# tick-mini-mk-4_2.net
KiCad netlist of a schematic drawn in EAGLE
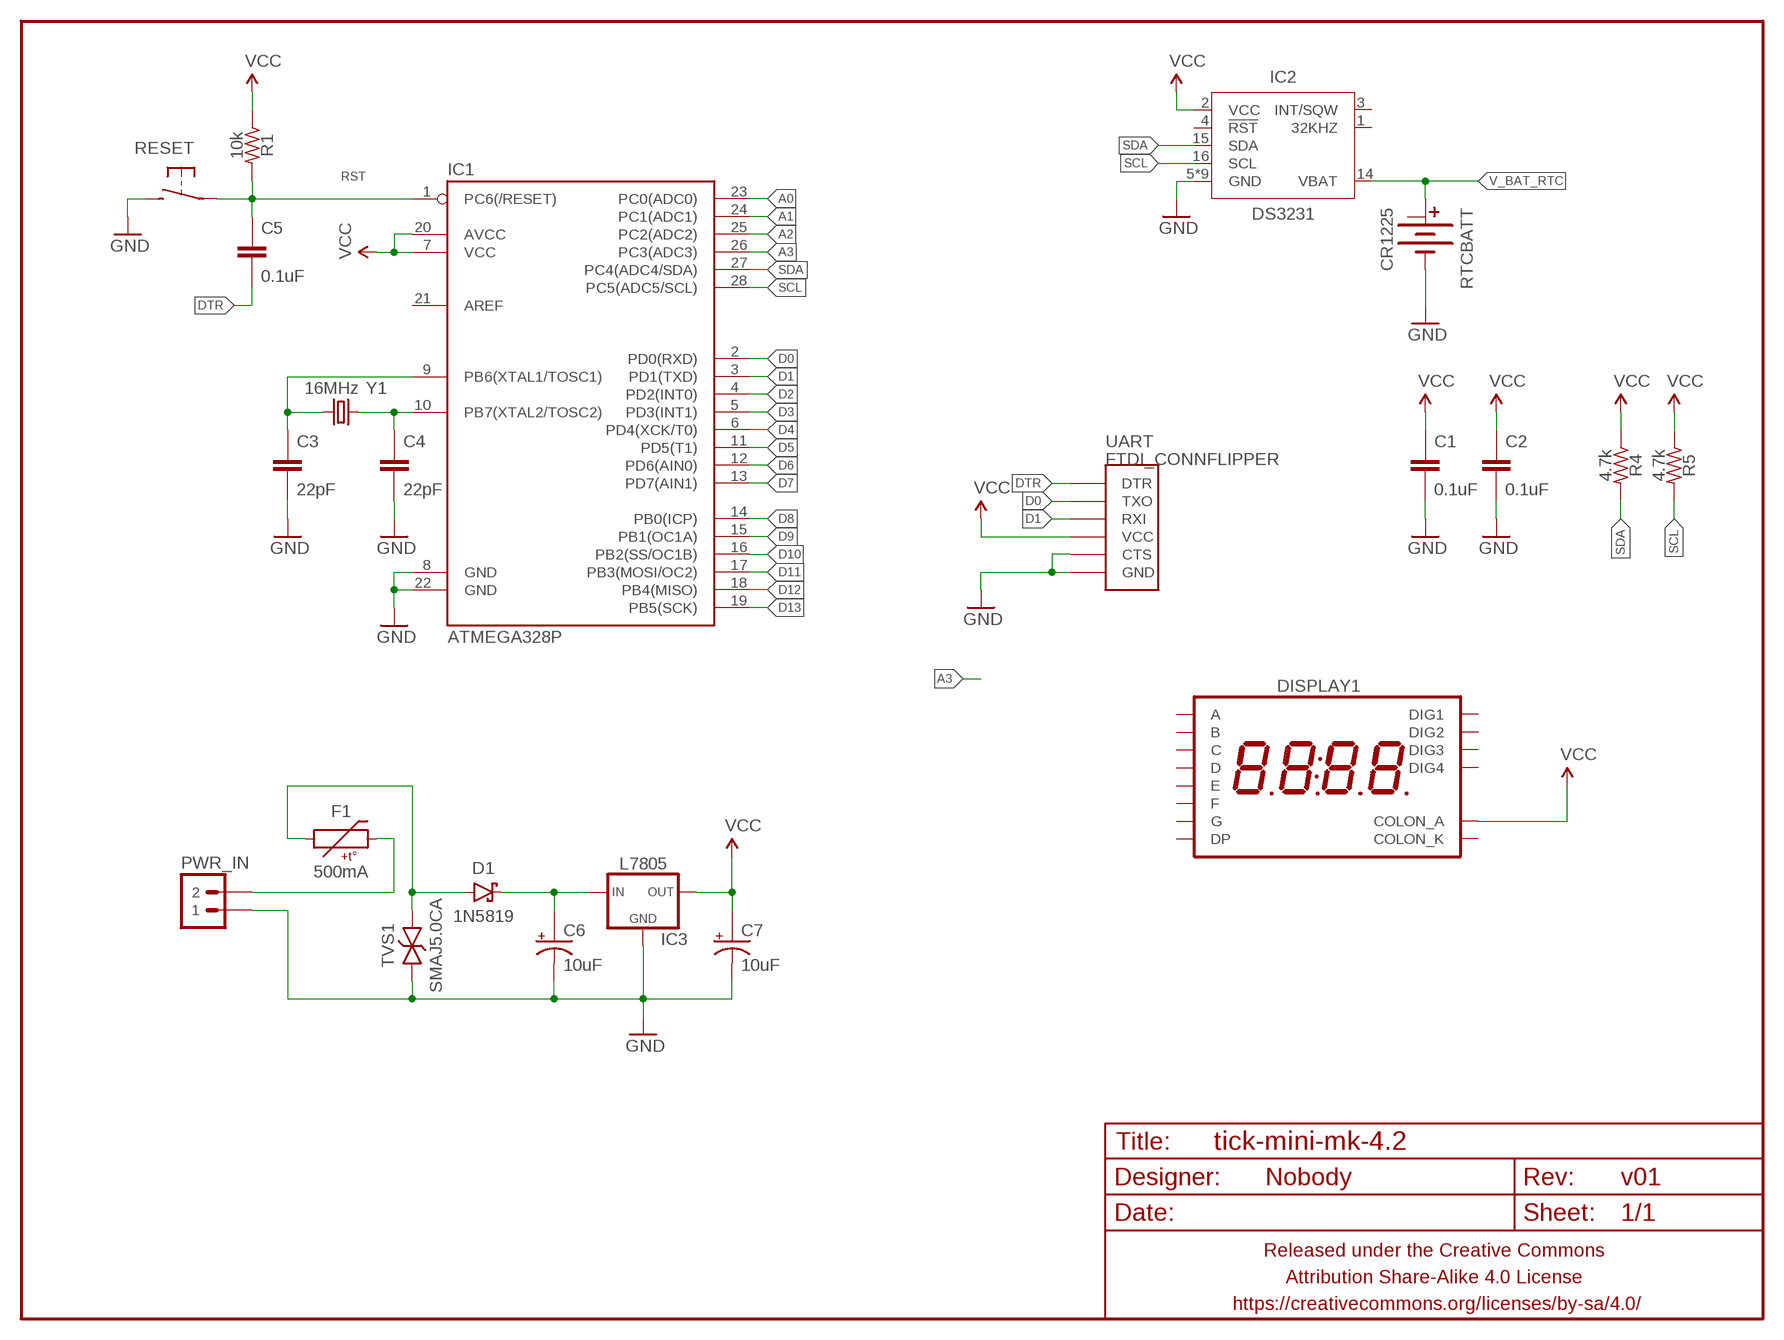
[diagram p0: schematic, sheet 1]

(export (version "E")
  (design (tool "Eeschema 10.0.6"))
  (components
    (comp (ref "C1")
      (value "0.1uF")
      (footprint "eagle-import:C025-024X044")
      (libsource (lib "eagle-import") (part "CAPACITOR-CERAMIC025-024X044"))
    )
    (comp (ref "C2")
      (value "0.1uF")
      (footprint "eagle-import:C025-024X044")
      (libsource (lib "eagle-import") (part "CAPACITOR-CERAMIC025-024X044"))
    )
    (comp (ref "C3")
      (value "22pF")
      (footprint "eagle-import:C025-024X044")
      (libsource (lib "eagle-import") (part "CAPACITOR-CERAMIC025-024X044"))
    )
    (comp (ref "C4")
      (value "22pF")
      (footprint "eagle-import:C025-024X044")
      (libsource (lib "eagle-import") (part "CAPACITOR-CERAMIC025-024X044"))
    )
    (comp (ref "C5")
      (value "0.1uF")
      (footprint "eagle-import:C025-024X044")
      (libsource (lib "eagle-import") (part "CAPACITOR-CERAMIC025-024X044"))
    )
    (comp (ref "C6")
      (value "10uF")
      (footprint "eagle-import:E2-5")
      (libsource (lib "eagle-import") (part "CAPACITOR-POLARIZEDE2-5"))
    )
    (comp (ref "C7")
      (value "10uF")
      (footprint "eagle-import:E2-5")
      (libsource (lib "eagle-import") (part "CAPACITOR-POLARIZEDE2-5"))
    )
    (comp (ref "D1")
      (value "1N5819")
      (footprint "eagle-import:DIODE-10.16MM")
      (libsource (lib "eagle-import") (part "DIODE-SCHOTTKYPTH-10.16MM"))
    )
    (comp (ref "DISPLAY1")
      (value "7SEG_4DIGIT_COLON14.2MM-CC-NS")
      (footprint "eagle-import:7SEG_4DIG_NS")
      (libsource (lib "eagle-import") (part "7SEG_4DIGIT_COLON14.2MM-CC-NS"))
    )
    (comp (ref "F1")
      (value "500mA")
      (footprint "eagle-import:PTC-PTH-5.08MM")
      (libsource (lib "eagle-import") (part "PTCPTH-5.08MM"))
    )
    (comp (ref "FRAME1")
      (value "FRAME-LETTERNO_PACKAGE")
      (footprint "eagle-import:DUMMY")
      (fields (field (name "DESIGNER") "Nobody"))
      (libsource (lib "eagle-import") (part "FRAME-LETTERNO_PACKAGE"))
    )
    (comp (ref "IC1")
      (value "ATMEGA328P")
      (footprint "eagle-import:DIL28-3")
      (libsource (lib "eagle-import") (part "ATMEGA328P_PDIP"))
    )
    (comp (ref "IC2")
      (value "DS3231")
      (footprint "eagle-import:SO16W")
      (libsource (lib "eagle-import") (part "DS3231"))
    )
    (comp (ref "IC3")
      (value "L7805")
      (footprint "eagle-import:TO-92-AMMO")
      (libsource (lib "eagle-import") (part "V_REG_78XXTO-92-INLINE"))
    )
    (comp (ref "PWR_IN")
      (value "M02JST-PTH-RA-R+")
      (footprint "eagle-import:JST-2-PH-RA-PTH-R+")
      (libsource (lib "eagle-import") (part "M02JST-PTH-RA-R+"))
    )
    (comp (ref "R1")
      (value "10k")
      (footprint "eagle-import:RESISTOR-AXIAL-PTH-5.08MM")
      (libsource (lib "eagle-import") (part "RESISTORPTH-AXIAL-5.08MM"))
    )
    (comp (ref "R4")
      (value "4.7k")
      (footprint "eagle-import:RESISTOR-AXIAL-PTH-5.08MM")
      (libsource (lib "eagle-import") (part "RESISTORPTH-AXIAL-5.08MM"))
    )
    (comp (ref "R5")
      (value "4.7k")
      (footprint "eagle-import:RESISTOR-AXIAL-PTH-5.08MM")
      (libsource (lib "eagle-import") (part "RESISTORPTH-AXIAL-5.08MM"))
    )
    (comp (ref "RESET")
      (value "SPST-NO-TACT3MM-PTH-SMALL-PADS")
      (footprint "eagle-import:DTS-3-SMALL-PADS")
      (libsource (lib "eagle-import") (part "SPST-NO-TACT3MM-PTH-SMALL-PADS"))
    )
    (comp (ref "RTCBATT")
      (value "CR1225")
      (footprint "eagle-import:BATTCON_12MM_SMD")
      (libsource (lib "eagle-import") (part "BATTERY-COINCR1225_SMD_SMALLER"))
    )
    (comp (ref "TVS1")
      (value "SMAJ5.0CA")
      (footprint "eagle-import:DO-41-TVS-BI-10.16MM")
      (libsource (lib "eagle-import") (part "TVSDO-41-10.16MM"))
    )
    (comp (ref "UART")
      (value "FTDI_CONNFLIPPER")
      (footprint "eagle-import:FTDI_CONN_FLIP")
      (libsource (lib "eagle-import") (part "FTDI_CONNFLIPPER"))
    )
    (comp (ref "Y1")
      (value "16MHz")
      (footprint "eagle-import:HC49U-V")
      (libsource (lib "eagle-import") (part "CRYSTALHC49UV"))
    )
  )
  (nets
    (net (code "1") (name "/RST") (class "Default")
      (node (ref "C5") (pin "1") (pinfunction "1_1") (pintype "passive"))
      (node (ref "IC1") (pin "1") (pinfunction "PC6(/RESET)_1") (pintype "bidirectional"))
      (node (ref "R1") (pin "P$2") (pinfunction "2_P$2") (pintype "passive"))
      (node (ref "RESET") (pin "1") (pinfunction "1_1") (pintype "passive"))
    )
    (net (code "2") (name "A0") (class "Default")
      (node (ref "IC1") (pin "23") (pinfunction "PC0(ADC0)_23") (pintype "bidirectional"))
    )
    (net (code "3") (name "A1") (class "Default")
      (node (ref "IC1") (pin "24") (pinfunction "PC1(ADC1)_24") (pintype "bidirectional"))
    )
    (net (code "4") (name "A2") (class "Default")
      (node (ref "IC1") (pin "25") (pinfunction "PC2(ADC2)_25") (pintype "bidirectional"))
    )
    (net (code "5") (name "A3") (class "Default")
      (node (ref "IC1") (pin "26") (pinfunction "PC3(ADC3)_26") (pintype "bidirectional"))
    )
    (net (code "6") (name "D0") (class "Default")
      (node (ref "IC1") (pin "2") (pinfunction "PD0(RXD)_2") (pintype "bidirectional"))
      (node (ref "UART") (pin "TXO") (pinfunction "TXO_TXO") (pintype "bidirectional"))
    )
    (net (code "7") (name "D1") (class "Default")
      (node (ref "IC1") (pin "3") (pinfunction "PD1(TXD)_3") (pintype "bidirectional"))
      (node (ref "UART") (pin "RXI") (pinfunction "RXI_RXI") (pintype "bidirectional"))
    )
    (net (code "8") (name "D2") (class "Default")
      (node (ref "IC1") (pin "4") (pinfunction "PD2(INT0)_4") (pintype "bidirectional"))
    )
    (net (code "9") (name "D3") (class "Default")
      (node (ref "IC1") (pin "5") (pinfunction "PD3(INT1)_5") (pintype "bidirectional"))
    )
    (net (code "10") (name "D4") (class "Default")
      (node (ref "IC1") (pin "6") (pinfunction "PD4(XCK/T0)_6") (pintype "bidirectional"))
    )
    (net (code "11") (name "D5") (class "Default")
      (node (ref "IC1") (pin "11") (pinfunction "PD5(T1)_11") (pintype "bidirectional"))
    )
    (net (code "12") (name "D6") (class "Default")
      (node (ref "IC1") (pin "12") (pinfunction "PD6(AIN0)_12") (pintype "bidirectional"))
    )
    (net (code "13") (name "D7") (class "Default")
      (node (ref "IC1") (pin "13") (pinfunction "PD7(AIN1)_13") (pintype "bidirectional"))
    )
    (net (code "14") (name "D8") (class "Default")
      (node (ref "IC1") (pin "14") (pinfunction "PB0(ICP)_14") (pintype "bidirectional"))
    )
    (net (code "15") (name "D9") (class "Default")
      (node (ref "IC1") (pin "15") (pinfunction "PB1(OC1A)_15") (pintype "bidirectional"))
    )
    (net (code "16") (name "D10") (class "Default")
      (node (ref "IC1") (pin "16") (pinfunction "PB2(SS/OC1B)_16") (pintype "bidirectional"))
    )
    (net (code "17") (name "D11") (class "Default")
      (node (ref "IC1") (pin "17") (pinfunction "PB3(MOSI/OC2)_17") (pintype "bidirectional"))
    )
    (net (code "18") (name "D12") (class "Default")
      (node (ref "IC1") (pin "18") (pinfunction "PB4(MISO)_18") (pintype "bidirectional"))
    )
    (net (code "19") (name "D13") (class "Default")
      (node (ref "IC1") (pin "19") (pinfunction "PB5(SCK)_19") (pintype "bidirectional"))
    )
    (net (code "20") (name "DTR") (class "Default")
      (node (ref "C5") (pin "2") (pinfunction "2_2") (pintype "passive"))
      (node (ref "UART") (pin "DTR") (pinfunction "DTR_DTR") (pintype "bidirectional"))
    )
    (net (code "21") (name "GND") (class "Default")
      (node (ref "C1") (pin "2") (pinfunction "2_2") (pintype "passive"))
      (node (ref "C2") (pin "2") (pinfunction "2_2") (pintype "passive"))
      (node (ref "C3") (pin "2") (pinfunction "2_2") (pintype "passive"))
      (node (ref "C4") (pin "2") (pinfunction "2_2") (pintype "passive"))
      (node (ref "C6") (pin "-") (pinfunction "-_-") (pintype "passive"))
      (node (ref "C7") (pin "-") (pinfunction "-_-") (pintype "passive"))
      (node (ref "IC1") (pin "22") (pinfunction "GND_22") (pintype "bidirectional"))
      (node (ref "IC1") (pin "8") (pinfunction "GND_8") (pintype "bidirectional"))
      (node (ref "IC2") (pin "10") (pinfunction "GND_10") (pintype "bidirectional"))
      (node (ref "IC2") (pin "11") (pinfunction "GND_11") (pintype "bidirectional"))
      (node (ref "IC2") (pin "12") (pinfunction "GND_12") (pintype "bidirectional"))
      (node (ref "IC2") (pin "13") (pinfunction "GND_13") (pintype "bidirectional"))
      (node (ref "IC2") (pin "5") (pinfunction "GND_5") (pintype "bidirectional"))
      (node (ref "IC2") (pin "6") (pinfunction "GND_6") (pintype "bidirectional"))
      (node (ref "IC2") (pin "7") (pinfunction "GND_7") (pintype "bidirectional"))
      (node (ref "IC2") (pin "8") (pinfunction "GND_8") (pintype "bidirectional"))
      (node (ref "IC2") (pin "9") (pinfunction "GND_9") (pintype "bidirectional"))
      (node (ref "IC3") (pin "2") (pinfunction "GND_2") (pintype "bidirectional"))
      (node (ref "PWR_IN") (pin "1") (pinfunction "1_1") (pintype "passive"))
      (node (ref "RESET") (pin "2") (pinfunction "2_2") (pintype "passive"))
      (node (ref "RTCBATT") (pin "-") (pinfunction "-_-") (pintype "bidirectional"))
      (node (ref "TVS1") (pin "P$1") (pinfunction "1_P$1") (pintype "passive"))
      (node (ref "UART") (pin "CTS") (pinfunction "CTS_CTS") (pintype "bidirectional"))
      (node (ref "UART") (pin "GND") (pinfunction "GND_GND") (pintype "bidirectional"))
    )
    (net (code "22") (name "Net-(F1-1)") (class "Default")
      (node (ref "D1") (pin "A") (pinfunction "A_A") (pintype "passive"))
      (node (ref "F1") (pin "P$1") (pinfunction "1_P$1") (pintype "passive"))
      (node (ref "TVS1") (pin "P$2") (pinfunction "2_P$2") (pintype "passive"))
    )
    (net (code "23") (name "Net-(F1-2)") (class "Default")
      (node (ref "F1") (pin "P$2") (pinfunction "2_P$2") (pintype "passive"))
      (node (ref "PWR_IN") (pin "2") (pinfunction "2_2") (pintype "passive"))
    )
    (net (code "24") (name "Net-(IC1-PB6(XTAL1{slash}TOSC1))") (class "Default")
      (node (ref "C3") (pin "1") (pinfunction "1_1") (pintype "passive"))
      (node (ref "IC1") (pin "9") (pinfunction "PB6(XTAL1/TOSC1)_9") (pintype "bidirectional"))
      (node (ref "Y1") (pin "2") (pinfunction "2_2") (pintype "passive"))
    )
    (net (code "25") (name "Net-(IC1-PB7(XTAL2{slash}TOSC2))") (class "Default")
      (node (ref "C4") (pin "1") (pinfunction "1_1") (pintype "passive"))
      (node (ref "IC1") (pin "10") (pinfunction "PB7(XTAL2/TOSC2)_10") (pintype "bidirectional"))
      (node (ref "Y1") (pin "1") (pinfunction "1_1") (pintype "passive"))
    )
    (net (code "26") (name "Net-(IC3-IN)") (class "Default")
      (node (ref "C6") (pin "+") (pinfunction "+_+") (pintype "passive"))
      (node (ref "D1") (pin "C") (pinfunction "C_C") (pintype "passive"))
      (node (ref "IC3") (pin "1") (pinfunction "IN_1") (pintype "bidirectional"))
    )
    (net (code "27") (name "SCL") (class "Default")
      (node (ref "IC1") (pin "28") (pinfunction "PC5(ADC5/SCL)_28") (pintype "bidirectional"))
      (node (ref "IC2") (pin "16") (pinfunction "SCL_16") (pintype "bidirectional"))
      (node (ref "R5") (pin "P$2") (pinfunction "2_P$2") (pintype "passive"))
    )
    (net (code "28") (name "SDA") (class "Default")
      (node (ref "IC1") (pin "27") (pinfunction "PC4(ADC4/SDA)_27") (pintype "bidirectional"))
      (node (ref "IC2") (pin "15") (pinfunction "SDA_15") (pintype "bidirectional"))
      (node (ref "R4") (pin "P$2") (pinfunction "2_P$2") (pintype "passive"))
    )
    (net (code "29") (name "VCC") (class "Default")
      (node (ref "C1") (pin "1") (pinfunction "1_1") (pintype "passive"))
      (node (ref "C2") (pin "1") (pinfunction "1_1") (pintype "passive"))
      (node (ref "C7") (pin "+") (pinfunction "+_+") (pintype "passive"))
      (node (ref "DISPLAY1") (pin "P$8") (pinfunction "COLON_A_P$8") (pintype "passive"))
      (node (ref "IC1") (pin "20") (pinfunction "AVCC_20") (pintype "bidirectional"))
      (node (ref "IC1") (pin "7") (pinfunction "VCC_7") (pintype "bidirectional"))
      (node (ref "IC2") (pin "2") (pinfunction "VCC_2") (pintype "bidirectional"))
      (node (ref "IC3") (pin "3") (pinfunction "OUT_3") (pintype "bidirectional"))
      (node (ref "R1") (pin "P$1") (pinfunction "1_P$1") (pintype "passive"))
      (node (ref "R4") (pin "P$1") (pinfunction "1_P$1") (pintype "passive"))
      (node (ref "R5") (pin "P$1") (pinfunction "1_P$1") (pintype "passive"))
      (node (ref "UART") (pin "VCC") (pinfunction "VCC_VCC") (pintype "bidirectional"))
    )
    (net (code "30") (name "V_BAT_RTC") (class "Default")
      (node (ref "IC2") (pin "14") (pinfunction "VBAT_14") (pintype "bidirectional"))
      (node (ref "RTCBATT") (pin "+@1") (pinfunction "+_+@1") (pintype "bidirectional"))
    )
    (net (code "31") (name "unconnected-(DISPLAY1-A-PadP$13)") (class "Default")
      (node (ref "DISPLAY1") (pin "P$13") (pinfunction "A_P$13") (pintype "passive"))
    )
    (net (code "32") (name "unconnected-(DISPLAY1-B-PadP$9)") (class "Default")
      (node (ref "DISPLAY1") (pin "P$9") (pinfunction "B_P$9") (pintype "passive"))
    )
    (net (code "33") (name "unconnected-(DISPLAY1-C-PadP$4)") (class "Default")
      (node (ref "DISPLAY1") (pin "P$4") (pinfunction "C_P$4") (pintype "passive"))
    )
    (net (code "34") (name "unconnected-(DISPLAY1-COLON_K-PadP$7)") (class "Default")
      (node (ref "DISPLAY1") (pin "P$7") (pinfunction "COLON_K_P$7") (pintype "passive"))
    )
    (net (code "35") (name "unconnected-(DISPLAY1-D-PadP$2)") (class "Default")
      (node (ref "DISPLAY1") (pin "P$2") (pinfunction "D_P$2") (pintype "passive"))
    )
    (net (code "36") (name "unconnected-(DISPLAY1-DIG1-PadP$14)") (class "Default")
      (node (ref "DISPLAY1") (pin "P$14") (pinfunction "DIG1_P$14") (pintype "passive"))
    )
    (net (code "37") (name "unconnected-(DISPLAY1-DIG2-PadP$11)") (class "Default")
      (node (ref "DISPLAY1") (pin "P$11") (pinfunction "DIG2_P$11") (pintype "passive"))
    )
    (net (code "38") (name "unconnected-(DISPLAY1-DIG3-PadP$10)") (class "Default")
      (node (ref "DISPLAY1") (pin "P$10") (pinfunction "DIG3_P$10") (pintype "passive"))
    )
    (net (code "39") (name "unconnected-(DISPLAY1-DIG4-PadP$6)") (class "Default")
      (node (ref "DISPLAY1") (pin "P$6") (pinfunction "DIG4_P$6") (pintype "passive"))
    )
    (net (code "40") (name "unconnected-(DISPLAY1-DP-PadP$3)") (class "Default")
      (node (ref "DISPLAY1") (pin "P$3") (pinfunction "DP_P$3") (pintype "passive"))
    )
    (net (code "41") (name "unconnected-(DISPLAY1-E-PadP$1)") (class "Default")
      (node (ref "DISPLAY1") (pin "P$1") (pinfunction "E_P$1") (pintype "passive"))
    )
    (net (code "42") (name "unconnected-(DISPLAY1-F-PadP$12)") (class "Default")
      (node (ref "DISPLAY1") (pin "P$12") (pinfunction "F_P$12") (pintype "passive"))
    )
    (net (code "43") (name "unconnected-(DISPLAY1-G-PadP$5)") (class "Default")
      (node (ref "DISPLAY1") (pin "P$5") (pinfunction "G_P$5") (pintype "passive"))
    )
    (net (code "44") (name "unconnected-(IC1-AREF-Pad21)") (class "Default")
      (node (ref "IC1") (pin "21") (pinfunction "AREF_21") (pintype "bidirectional"))
    )
    (net (code "45") (name "unconnected-(IC2-32KHZ-Pad1)") (class "Default")
      (node (ref "IC2") (pin "1") (pinfunction "32KHZ_1") (pintype "bidirectional"))
    )
    (net (code "46") (name "unconnected-(IC2-INT{slash}SQW-Pad3)") (class "Default")
      (node (ref "IC2") (pin "3") (pinfunction "INT/SQW_3") (pintype "bidirectional"))
    )
    (net (code "47") (name "unconnected-(IC2-~{RST}-Pad4)") (class "Default")
      (node (ref "IC2") (pin "4") (pinfunction "~{RST}_4") (pintype "bidirectional"))
    )
    (net (code "48") (name "unconnected-(RTCBATT-+1-Pad+@2)") (class "Default")
      (node (ref "RTCBATT") (pin "+@2") (pinfunction "+1_+@2") (pintype "bidirectional"))
    )
  )
)
